# 3_3v_BUCK.net
KiCad netlist of a schematic drawn in Altium Designer
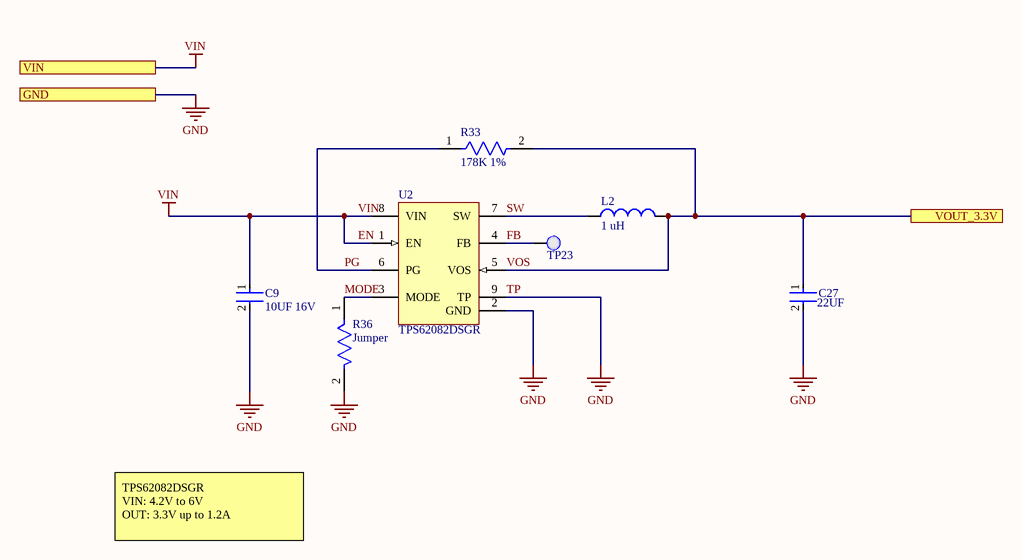
[diagram p0: 3.3v_BUCK.SchDoc]

(export (version "E")
  (design (tool "Eeschema 10.0.6"))
  (components
    (comp (ref "C9")
      (value "10UF 16V")
      (footprint "FP-CC0603-DB-MFG")
      (description "CAP CER 10UF 6.3V X5R 0603")
      (fields (field (name "TOLERANCE") "20%"))
      (libsource (lib "Altium Content Vault") (part "e9c51b7dd13d4faca003ae77663ab08"))
    )
    (comp (ref "C27")
      (value "22UF")
      (footprint "FP-CC0805-0_2-1_45-IPC_C")
      (description "CAP CER 22UF 25V X5R 0805")
      (fields (field (name "TOLERANCE") "20%"))
      (libsource (lib "Altium Content Vault") (part "11868f565c42a9108669ba33697ecf6"))
    )
    (comp (ref "L2")
      (value "1 uH")
      (footprint "COIL-XFL4020_V")
      (description "Shielded Power Inductor, 1 uH, 64 MHz, -40 to 125 degC, 2-Pin SMD, RoHS, Tape and Reel")
      (fields (field (name "MANUFACTURER") "Coilcraft") (field (name "TOLERANCE") "20%"))
      (libsource (lib "Altium Content Vault") (part "IND-2"))
    )
    (comp (ref "R33")
      (value "178K 1%")
      (footprint "FP-RMCF1210-IPC_B")
      (description "178kΩ ±1% 0.5W 1210 Thick Film Chip Resistor AEC-Q200 compliant")
      (fields (field (name "TOLERANCE") "1%"))
      (libsource (lib "Altium Content Vault") (part "1029c3af85768c4190bb7ad29bc67b5"))
    )
    (comp (ref "R36")
      (value "Jumper")
      (footprint "FP-RMCF0603-MFG")
      (description "RES 0 OHM JUMPER 1/10W 0603")
      (fields
        (field (name "MANUFACTURER PART NUMBER") "RMCF0603ZT0R00")
        (field (name "OCTOPART") "https://octopart.com/rmcf0603zt0r00-stackpole+electronics-19213618")
      )
      (libsource (lib "Altium Content Vault") (part "1029c3af85768c4190bb7ad29bc67b5"))
    )
    (comp (ref "TP23")
      (value "Test Point 0.1\"")
      (footprint "Test Point 0.1\"-Footprint-1")
      (libsource (lib "University of Pennsylvania (ESE Labs)") (part "Test Point 0.1{dblquote}-Symbol-1"))
    )
    (comp (ref "U2")
      (value "TPS62082DSGR")
      (footprint "DSG0008A_V")
      (fields (field (name "MANUFACTURER") "Texas Instruments"))
      (libsource (lib "Altium Content Vault") (part "TI-TPS62082DSG8-1600X900TP"))
    )
  )
  (nets
    (net (code "1") (name "/FB") (class "Default")
      (node (ref "TP23") (pin "1") (pinfunction "PAD_1") (pintype "passive"))
      (node (ref "U2") (pin "4") (pinfunction "FB_4") (pintype "passive"))
    )
    (net (code "2") (name "/MODE") (class "Default")
      (node (ref "R36") (pin "1") (pinfunction "1_1") (pintype "passive"))
      (node (ref "U2") (pin "3") (pinfunction "MODE_3") (pintype "power_in"))
    )
    (net (code "3") (name "/PG") (class "Default")
      (node (ref "R33") (pin "1") (pinfunction "1_1") (pintype "passive"))
      (node (ref "U2") (pin "6") (pinfunction "PG_6") (pintype "tri_state"))
    )
    (net (code "4") (name "/SW") (class "Default")
      (node (ref "L2") (pin "1") (pinfunction "1_1") (pintype "passive"))
      (node (ref "U2") (pin "7") (pinfunction "SW_7") (pintype "power_in"))
    )
    (net (code "5") (name "/VOS") (class "Default")
      (node (ref "C27") (pin "1") (pinfunction "1_1") (pintype "passive"))
      (node (ref "L2") (pin "2") (pinfunction "2_2") (pintype "passive"))
      (node (ref "R33") (pin "2") (pinfunction "2_2") (pintype "passive"))
      (node (ref "U2") (pin "5") (pinfunction "VOS_5") (pintype "input"))
    )
    (net (code "6") (name "GND") (class "Default")
      (node (ref "C27") (pin "2") (pinfunction "2_2") (pintype "passive"))
      (node (ref "C9") (pin "2") (pinfunction "2_2") (pintype "passive"))
      (node (ref "R36") (pin "2") (pinfunction "2_2") (pintype "passive"))
      (node (ref "U2") (pin "2") (pinfunction "GND_2") (pintype "power_in"))
      (node (ref "U2") (pin "9") (pinfunction "TP_9") (pintype "power_in"))
    )
    (net (code "7") (name "VIN") (class "Default")
      (node (ref "C9") (pin "1") (pinfunction "1_1") (pintype "passive"))
      (node (ref "U2") (pin "1") (pinfunction "EN_1") (pintype "input"))
      (node (ref "U2") (pin "8") (pinfunction "VIN_8") (pintype "power_in"))
    )
  )
)
